# pycomDaughterBoard.net
KiCad netlist of a schematic drawn in EAGLE
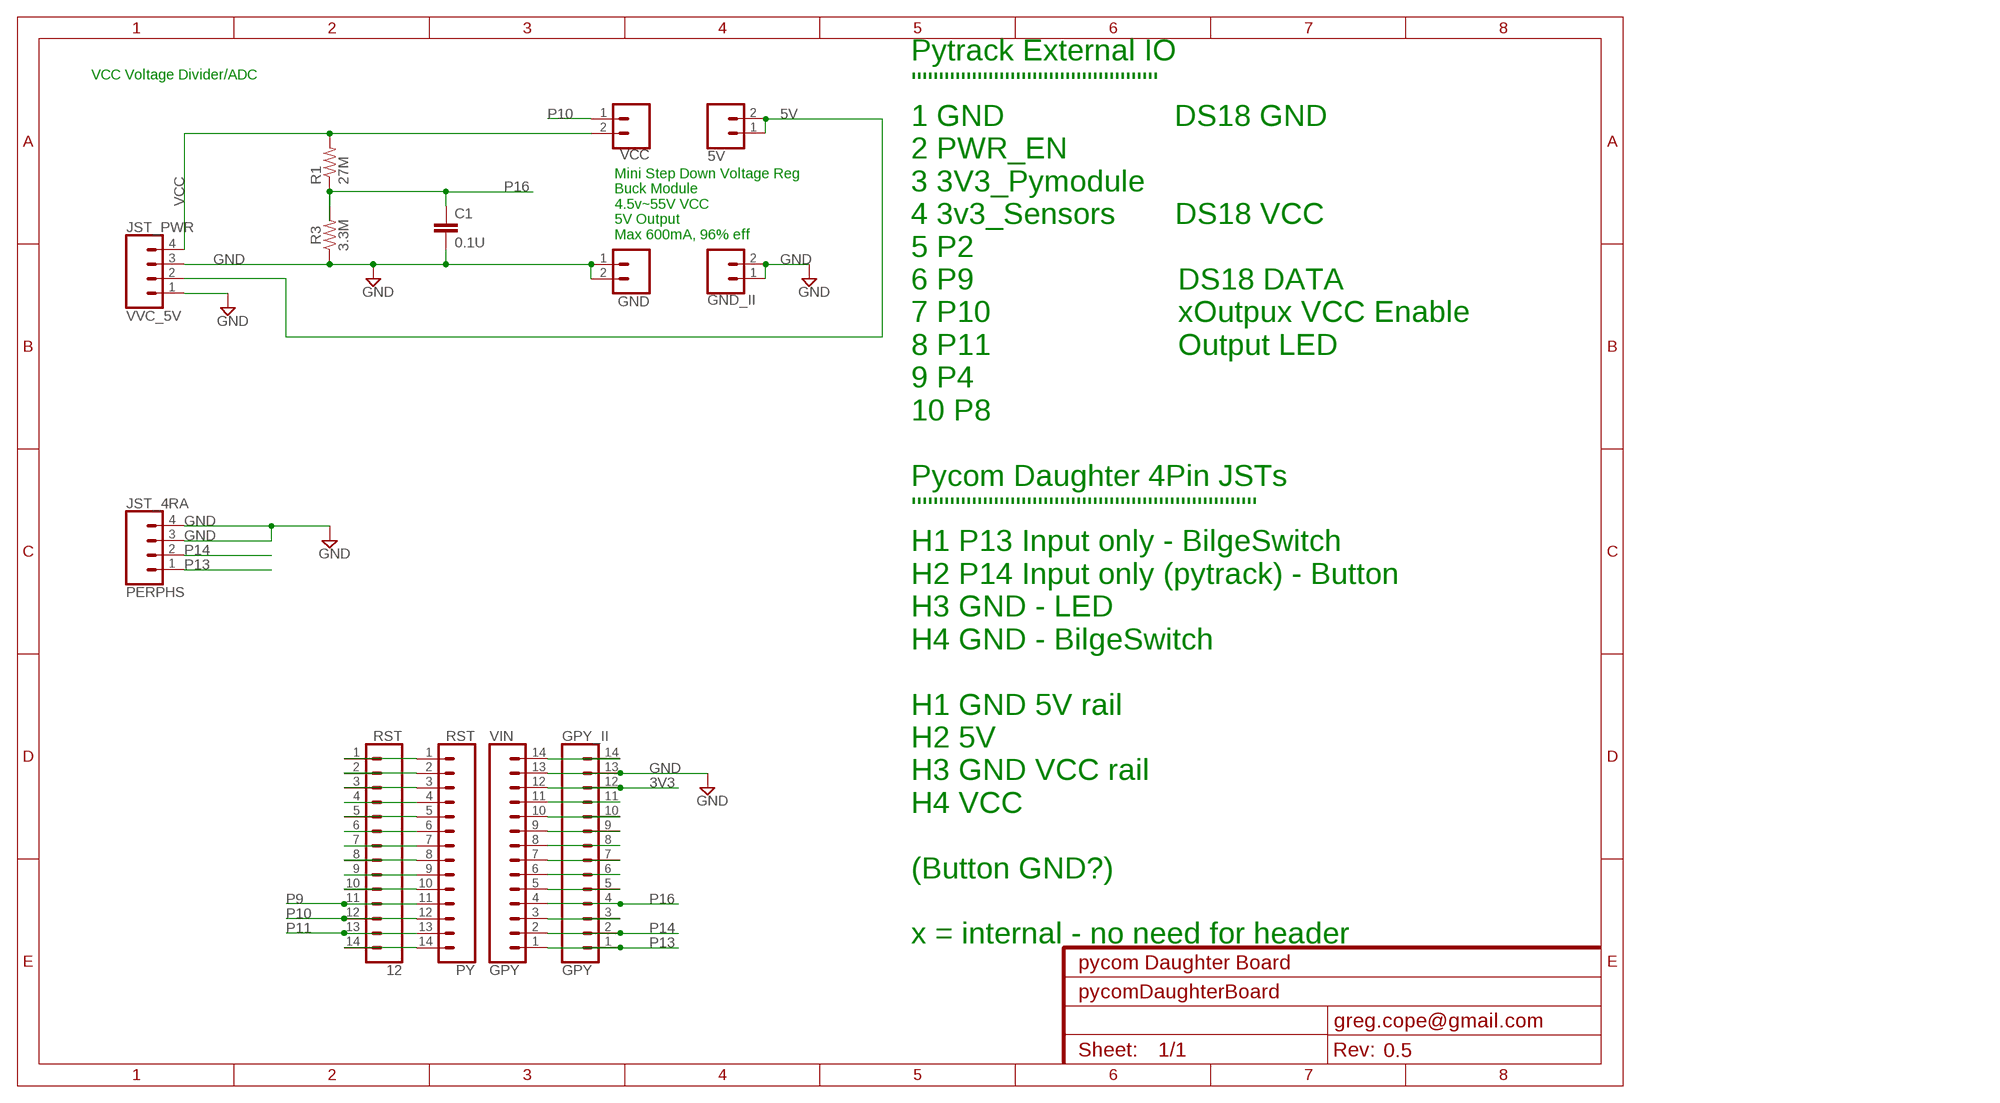
[diagram p0: schematic, sheet 1]

(export (version "E")
  (design (tool "Eeschema 10.0.6"))
  (components
    (comp (ref "5V")
      (value "5V")
      (footprint "eagle-import:1X02")
      (libsource (lib "eagle-import") (part "CONN_02"))
    )
    (comp (ref "12")
      (value "RST")
      (footprint "eagle-import:1X14")
      (libsource (lib "eagle-import") (part "CONN_14"))
    )
    (comp (ref "C1")
      (value "0.1U")
      (footprint "eagle-import:CAP-PTH-SMALL-KIT")
      (libsource (lib "eagle-import") (part "0.1UF-KIT-EZ-50V-20%"))
    )
    (comp (ref "GND")
      (value "GND")
      (footprint "eagle-import:1X02")
      (libsource (lib "eagle-import") (part "CONN_02"))
    )
    (comp (ref "GND_II")
      (value "GND")
      (footprint "eagle-import:1X02")
      (libsource (lib "eagle-import") (part "CONN_02"))
    )
    (comp (ref "GPY_II")
      (value "GPY")
      (footprint "eagle-import:1X14")
      (libsource (lib "eagle-import") (part "CONN_14"))
    )
    (comp (ref "JST_4RA")
      (value "PERPHS")
      (footprint "eagle-import:JST-4-PTH")
      (libsource (lib "eagle-import") (part "CONN_04JST-PTH"))
    )
    (comp (ref "JST_PWR")
      (value "VVC_5V")
      (footprint "eagle-import:JST-4-PTH")
      (libsource (lib "eagle-import") (part "CONN_04JST-PTH"))
    )
    (comp (ref "PY")
      (value "RST")
      (footprint "eagle-import:1X14")
      (libsource (lib "eagle-import") (part "CONN_14"))
    )
    (comp (ref "R1")
      (value "27M")
      (footprint "eagle-import:0309_12")
      (libsource (lib "eagle-import") (part "R-US_0309/12"))
    )
    (comp (ref "R3")
      (value "3.3M")
      (footprint "eagle-import:AXIAL-0.3")
      (libsource (lib "eagle-import") (part "1KOHM-HORIZ-1/4W-1%"))
    )
    (comp (ref "VCC")
      (value "VCC")
      (footprint "eagle-import:1X02")
      (libsource (lib "eagle-import") (part "CONN_02"))
    )
    (comp (ref "VIN")
      (value "GPY")
      (footprint "eagle-import:1X14")
      (libsource (lib "eagle-import") (part "CONN_14"))
    )
  )
  (nets
    (net (code "1") (name "/3V3") (class "Default")
      (node (ref "GPY_II") (pin "12") (pinfunction "12_12") (pintype "passive"))
      (node (ref "VIN") (pin "12") (pinfunction "12_12") (pintype "passive"))
    )
    (net (code "2") (name "/5V") (class "Default")
      (node (ref "5V") (pin "1") (pinfunction "1_1") (pintype "passive"))
      (node (ref "5V") (pin "2") (pinfunction "2_2") (pintype "passive"))
      (node (ref "JST_PWR") (pin "2") (pinfunction "2_2") (pintype "passive"))
    )
    (net (code "3") (name "/P9") (class "Default")
      (node (ref "12") (pin "11") (pinfunction "11_11") (pintype "passive"))
      (node (ref "PY") (pin "11") (pinfunction "11_11") (pintype "passive"))
    )
    (net (code "4") (name "/P10") (class "Default")
      (node (ref "12") (pin "12") (pinfunction "12_12") (pintype "passive"))
      (node (ref "PY") (pin "12") (pinfunction "12_12") (pintype "passive"))
      (node (ref "VCC") (pin "1") (pinfunction "1_1") (pintype "passive"))
    )
    (net (code "5") (name "/P11") (class "Default")
      (node (ref "12") (pin "13") (pinfunction "13_13") (pintype "passive"))
      (node (ref "PY") (pin "13") (pinfunction "13_13") (pintype "passive"))
    )
    (net (code "6") (name "/P13") (class "Default")
      (node (ref "GPY_II") (pin "1") (pinfunction "1_1") (pintype "passive"))
      (node (ref "JST_4RA") (pin "1") (pinfunction "1_1") (pintype "passive"))
      (node (ref "VIN") (pin "1") (pinfunction "1_1") (pintype "passive"))
    )
    (net (code "7") (name "/P14") (class "Default")
      (node (ref "GPY_II") (pin "2") (pinfunction "2_2") (pintype "passive"))
      (node (ref "JST_4RA") (pin "2") (pinfunction "2_2") (pintype "passive"))
      (node (ref "VIN") (pin "2") (pinfunction "2_2") (pintype "passive"))
    )
    (net (code "8") (name "/P16") (class "Default")
      (node (ref "C1") (pin "1") (pinfunction "1_1") (pintype "passive"))
      (node (ref "GPY_II") (pin "4") (pinfunction "4_4") (pintype "passive"))
      (node (ref "R1") (pin "1") (pinfunction "1_1") (pintype "passive"))
      (node (ref "R3") (pin "P$2") (pinfunction "2_P$2") (pintype "passive"))
      (node (ref "VIN") (pin "4") (pinfunction "4_4") (pintype "passive"))
    )
    (net (code "9") (name "/VCC") (class "Default")
      (node (ref "JST_PWR") (pin "4") (pinfunction "4_4") (pintype "passive"))
      (node (ref "R1") (pin "2") (pinfunction "2_2") (pintype "passive"))
      (node (ref "VCC") (pin "2") (pinfunction "2_2") (pintype "passive"))
    )
    (net (code "10") (name "GND") (class "Default")
      (node (ref "C1") (pin "2") (pinfunction "2_2") (pintype "passive"))
      (node (ref "GND") (pin "1") (pinfunction "1_1") (pintype "passive"))
      (node (ref "GND") (pin "2") (pinfunction "2_2") (pintype "passive"))
      (node (ref "GND_II") (pin "1") (pinfunction "1_1") (pintype "passive"))
      (node (ref "GND_II") (pin "2") (pinfunction "2_2") (pintype "passive"))
      (node (ref "GPY_II") (pin "13") (pinfunction "13_13") (pintype "passive"))
      (node (ref "JST_4RA") (pin "3") (pinfunction "3_3") (pintype "passive"))
      (node (ref "JST_4RA") (pin "4") (pinfunction "4_4") (pintype "passive"))
      (node (ref "JST_PWR") (pin "1") (pinfunction "1_1") (pintype "passive"))
      (node (ref "JST_PWR") (pin "3") (pinfunction "3_3") (pintype "passive"))
      (node (ref "R3") (pin "P$1") (pinfunction "1_P$1") (pintype "passive"))
      (node (ref "VIN") (pin "13") (pinfunction "13_13") (pintype "passive"))
    )
    (net (code "11") (name "Net-(12-Pad1)") (class "Default")
      (node (ref "12") (pin "1") (pinfunction "1_1") (pintype "passive"))
      (node (ref "PY") (pin "1") (pinfunction "1_1") (pintype "passive"))
    )
    (net (code "12") (name "Net-(12-Pad2)") (class "Default")
      (node (ref "12") (pin "2") (pinfunction "2_2") (pintype "passive"))
      (node (ref "PY") (pin "2") (pinfunction "2_2") (pintype "passive"))
    )
    (net (code "13") (name "Net-(12-Pad3)") (class "Default")
      (node (ref "12") (pin "3") (pinfunction "3_3") (pintype "passive"))
      (node (ref "PY") (pin "3") (pinfunction "3_3") (pintype "passive"))
    )
    (net (code "14") (name "Net-(12-Pad4)") (class "Default")
      (node (ref "12") (pin "4") (pinfunction "4_4") (pintype "passive"))
      (node (ref "PY") (pin "4") (pinfunction "4_4") (pintype "passive"))
    )
    (net (code "15") (name "Net-(12-Pad5)") (class "Default")
      (node (ref "12") (pin "5") (pinfunction "5_5") (pintype "passive"))
      (node (ref "PY") (pin "5") (pinfunction "5_5") (pintype "passive"))
    )
    (net (code "16") (name "Net-(12-Pad6)") (class "Default")
      (node (ref "12") (pin "6") (pinfunction "6_6") (pintype "passive"))
      (node (ref "PY") (pin "6") (pinfunction "6_6") (pintype "passive"))
    )
    (net (code "17") (name "Net-(12-Pad7)") (class "Default")
      (node (ref "12") (pin "7") (pinfunction "7_7") (pintype "passive"))
      (node (ref "PY") (pin "7") (pinfunction "7_7") (pintype "passive"))
    )
    (net (code "18") (name "Net-(12-Pad8)") (class "Default")
      (node (ref "12") (pin "8") (pinfunction "8_8") (pintype "passive"))
      (node (ref "PY") (pin "8") (pinfunction "8_8") (pintype "passive"))
    )
    (net (code "19") (name "Net-(12-Pad9)") (class "Default")
      (node (ref "12") (pin "9") (pinfunction "9_9") (pintype "passive"))
      (node (ref "PY") (pin "9") (pinfunction "9_9") (pintype "passive"))
    )
    (net (code "20") (name "Net-(12-Pad10)") (class "Default")
      (node (ref "12") (pin "10") (pinfunction "10_10") (pintype "passive"))
      (node (ref "PY") (pin "10") (pinfunction "10_10") (pintype "passive"))
    )
    (net (code "21") (name "Net-(12-Pad14)") (class "Default")
      (node (ref "12") (pin "14") (pinfunction "14_14") (pintype "passive"))
      (node (ref "PY") (pin "14") (pinfunction "14_14") (pintype "passive"))
    )
    (net (code "22") (name "Net-(GPY_II-Pad3)") (class "Default")
      (node (ref "GPY_II") (pin "3") (pinfunction "3_3") (pintype "passive"))
      (node (ref "VIN") (pin "3") (pinfunction "3_3") (pintype "passive"))
    )
    (net (code "23") (name "Net-(GPY_II-Pad5)") (class "Default")
      (node (ref "GPY_II") (pin "5") (pinfunction "5_5") (pintype "passive"))
      (node (ref "VIN") (pin "5") (pinfunction "5_5") (pintype "passive"))
    )
    (net (code "24") (name "Net-(GPY_II-Pad6)") (class "Default")
      (node (ref "GPY_II") (pin "6") (pinfunction "6_6") (pintype "passive"))
      (node (ref "VIN") (pin "6") (pinfunction "6_6") (pintype "passive"))
    )
    (net (code "25") (name "Net-(GPY_II-Pad7)") (class "Default")
      (node (ref "GPY_II") (pin "7") (pinfunction "7_7") (pintype "passive"))
      (node (ref "VIN") (pin "7") (pinfunction "7_7") (pintype "passive"))
    )
    (net (code "26") (name "Net-(GPY_II-Pad8)") (class "Default")
      (node (ref "GPY_II") (pin "8") (pinfunction "8_8") (pintype "passive"))
      (node (ref "VIN") (pin "8") (pinfunction "8_8") (pintype "passive"))
    )
    (net (code "27") (name "Net-(GPY_II-Pad9)") (class "Default")
      (node (ref "GPY_II") (pin "9") (pinfunction "9_9") (pintype "passive"))
      (node (ref "VIN") (pin "9") (pinfunction "9_9") (pintype "passive"))
    )
    (net (code "28") (name "Net-(GPY_II-Pad10)") (class "Default")
      (node (ref "GPY_II") (pin "10") (pinfunction "10_10") (pintype "passive"))
      (node (ref "VIN") (pin "10") (pinfunction "10_10") (pintype "passive"))
    )
    (net (code "29") (name "Net-(GPY_II-Pad11)") (class "Default")
      (node (ref "GPY_II") (pin "11") (pinfunction "11_11") (pintype "passive"))
      (node (ref "VIN") (pin "11") (pinfunction "11_11") (pintype "passive"))
    )
    (net (code "30") (name "Net-(GPY_II-Pad14)") (class "Default")
      (node (ref "GPY_II") (pin "14") (pinfunction "14_14") (pintype "passive"))
      (node (ref "VIN") (pin "14") (pinfunction "14_14") (pintype "passive"))
    )
  )
)
